# Mainboard_Encoder_Interface.net
KiCad netlist of a schematic drawn in Altium Designer
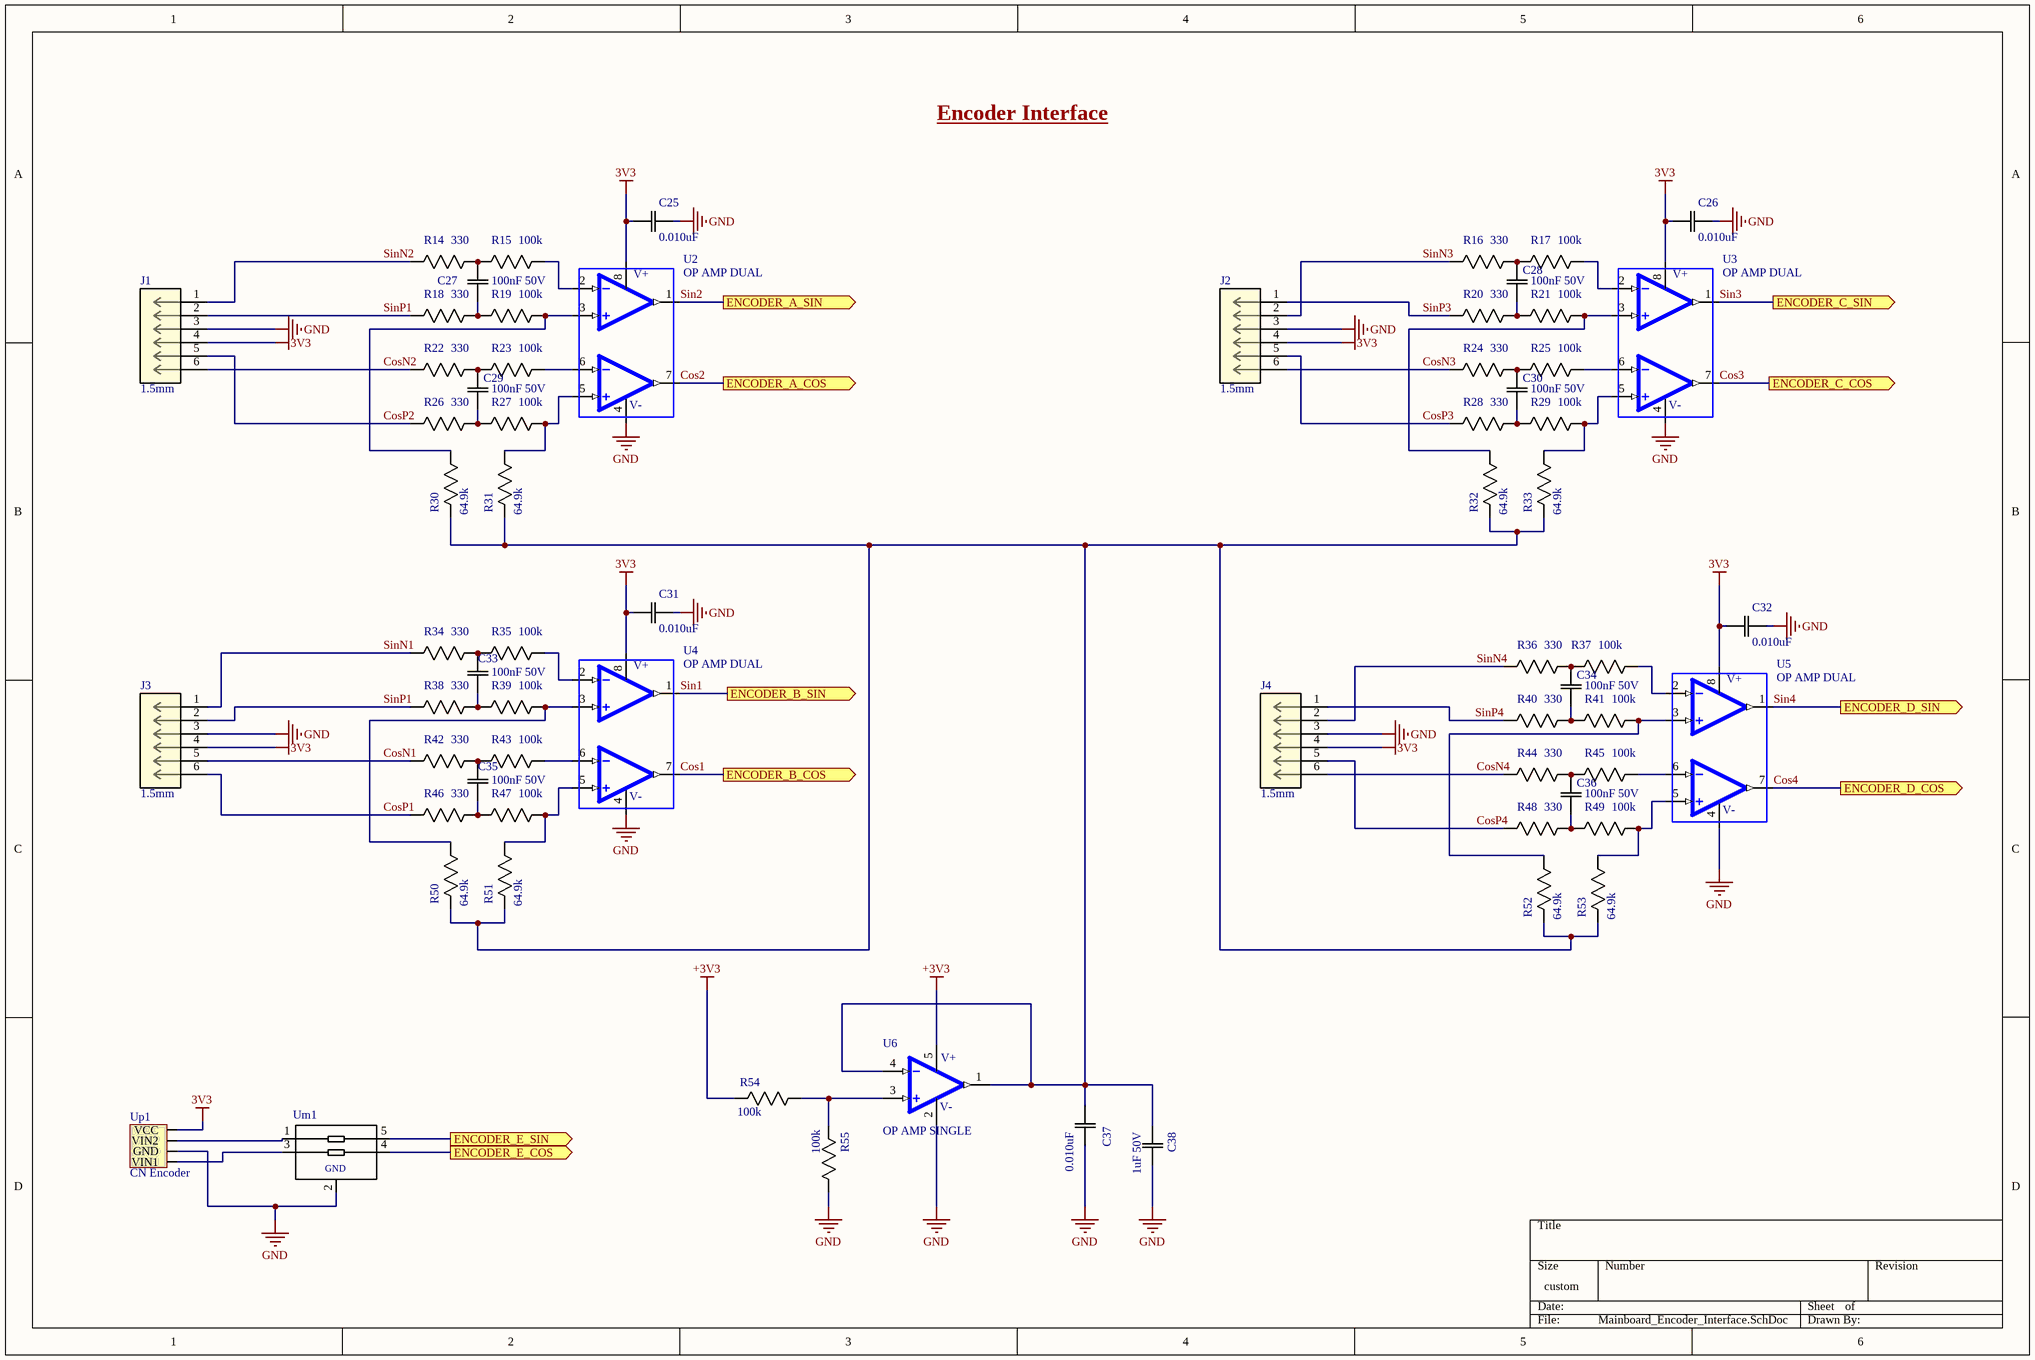
[diagram p0: Mainboard_Encoder_Interface.SchDoc]

(export (version "E")
  (design (tool "Eeschema 10.0.6"))
  (components
    (comp (ref "C25")
      (value "0.010uF")
      (footprint "0805")
      (description "CAP CER 0.010UF 50V X7R 0603/0805")
      (fields (field (name "TOLERANCE") "10%"))
      (libsource (lib "AltiumLibraries") (part "CAP 0.010uF 50V"))
    )
    (comp (ref "C26")
      (value "0.010uF")
      (footprint "0805")
      (description "CAP CER 0.010UF 50V X7R 0603/0805")
      (fields (field (name "TOLERANCE") "10%"))
      (libsource (lib "AltiumLibraries") (part "CAP 0.010uF 50V"))
    )
    (comp (ref "C27")
      (value "100nF 50V")
      (footprint "0805")
      (description "CAP CER 0.1UF 50V X7R 0805")
      (fields (field (name "TOLERANCE") "10%"))
      (libsource (lib "AltiumLibraries") (part "CAP 100nF 50V"))
    )
    (comp (ref "C28")
      (value "100nF 50V")
      (footprint "0805")
      (description "CAP CER 0.1UF 50V X7R 0805")
      (fields (field (name "TOLERANCE") "10%"))
      (libsource (lib "") (part "CAP 100nF 50V_2"))
    )
    (comp (ref "C29")
      (value "100nF 50V")
      (footprint "0805")
      (description "CAP CER 0.1UF 50V X7R 0805")
      (fields (field (name "TOLERANCE") "10%"))
      (libsource (lib "AltiumLibraries") (part "CAP 100nF 50V"))
    )
    (comp (ref "C30")
      (value "100nF 50V")
      (footprint "0805")
      (description "CAP CER 0.1UF 50V X7R 0805")
      (fields (field (name "TOLERANCE") "10%"))
      (libsource (lib "") (part "CAP 100nF 50V_2"))
    )
    (comp (ref "C31")
      (value "0.010uF")
      (footprint "0805")
      (description "CAP CER 0.010UF 50V X7R 0603/0805")
      (fields (field (name "TOLERANCE") "10%"))
      (libsource (lib "AltiumLibraries") (part "CAP 0.010uF 50V"))
    )
    (comp (ref "C32")
      (value "0.010uF")
      (footprint "0805")
      (description "CAP CER 0.010UF 50V X7R 0603/0805")
      (fields (field (name "TOLERANCE") "10%"))
      (libsource (lib "AltiumLibraries") (part "CAP 0.010uF 50V"))
    )
    (comp (ref "C33")
      (value "100nF 50V")
      (footprint "0805")
      (description "CAP CER 0.1UF 50V X7R 0805")
      (fields (field (name "TOLERANCE") "10%"))
      (libsource (lib "") (part "CAP 100nF 50V_1"))
    )
    (comp (ref "C34")
      (value "100nF 50V")
      (footprint "0805")
      (description "CAP CER 0.1UF 50V X7R 0805")
      (fields (field (name "TOLERANCE") "10%"))
      (libsource (lib "AltiumLibraries") (part "CAP 100nF 50V"))
    )
    (comp (ref "C35")
      (value "100nF 50V")
      (footprint "0805")
      (description "CAP CER 0.1UF 50V X7R 0805")
      (fields (field (name "TOLERANCE") "10%"))
      (libsource (lib "") (part "CAP 100nF 50V_1"))
    )
    (comp (ref "C36")
      (value "100nF 50V")
      (footprint "0805")
      (description "CAP CER 0.1UF 50V X7R 0805")
      (fields (field (name "TOLERANCE") "10%"))
      (libsource (lib "AltiumLibraries") (part "CAP 100nF 50V"))
    )
    (comp (ref "C37")
      (value "0.010uF")
      (footprint "0805")
      (description "CAP CER 0.010UF 50V X7R 0603/0805")
      (fields (field (name "TOLERANCE") "10%"))
      (libsource (lib "AltiumLibraries") (part "CAP 0.010uF 50V"))
    )
    (comp (ref "C38")
      (value "1uF 50V")
      (footprint "0805")
      (description "CAP CER 1UF 50V X7R 0805")
      (fields (field (name "TOLERANCE") "10%"))
      (libsource (lib "AltiumLibraries") (part "CAP 1uF 50V"))
    )
    (comp (ref "J1")
      (value "1.5mm")
      (footprint "6POS JST")
      (description "Conn Shrouded Header HDR 6 POS 1.5mm Solder RA Thru-Hole Box")
      (fields (field (name "MANUFACTURER") "JST") (field (name "MANUFACTURER PART NUMBER") "S6B-ZR(LF)(SN)"))
      (libsource (lib "AltiumLibraries") (part "CN 6POS JST RA"))
    )
    (comp (ref "J2")
      (value "1.5mm")
      (footprint "6POS JST")
      (description "Conn Shrouded Header HDR 6 POS 1.5mm Solder RA Thru-Hole Box")
      (fields (field (name "MANUFACTURER") "JST") (field (name "MANUFACTURER PART NUMBER") "S6B-ZR(LF)(SN)"))
      (libsource (lib "AltiumLibraries") (part "CN 6POS JST RA"))
    )
    (comp (ref "J3")
      (value "1.5mm")
      (footprint "6POS JST")
      (description "Conn Shrouded Header HDR 6 POS 1.5mm Solder RA Thru-Hole Box")
      (fields (field (name "MANUFACTURER") "JST") (field (name "MANUFACTURER PART NUMBER") "S6B-ZR(LF)(SN)"))
      (libsource (lib "AltiumLibraries") (part "CN 6POS JST RA"))
    )
    (comp (ref "J4")
      (value "1.5mm")
      (footprint "6POS JST")
      (description "Conn Shrouded Header HDR 6 POS 1.5mm Solder RA Thru-Hole Box")
      (fields (field (name "MANUFACTURER") "JST") (field (name "MANUFACTURER PART NUMBER") "S6B-ZR(LF)(SN)"))
      (libsource (lib "AltiumLibraries") (part "CN 6POS JST RA"))
    )
    (comp (ref "R14")
      (value "330")
      (footprint "0805")
      (description "RES SMD 330 OHM 1% 1/8W 0805")
      (fields (field (name "TOLERANCE") "1%"))
      (libsource (lib "AltiumLibraries") (part "RES 330.0 1/8W - 1%"))
    )
    (comp (ref "R15")
      (value "100k")
      (footprint "0805")
      (description "RES SMD 100K OHM 1% 1/8W 0805")
      (fields (field (name "TOLERANCE") "1%"))
      (libsource (lib "AltiumLibraries") (part "RES 100k 1/8W - 1%"))
    )
    (comp (ref "R16")
      (value "330")
      (footprint "0805")
      (description "RES SMD 330 OHM 1% 1/8W 0805")
      (fields (field (name "TOLERANCE") "1%"))
      (libsource (lib "AltiumLibraries") (part "RES 330.0 1/8W - 1%"))
    )
    (comp (ref "R17")
      (value "100k")
      (footprint "0805")
      (description "RES SMD 100K OHM 1% 1/8W 0805")
      (fields (field (name "TOLERANCE") "1%"))
      (libsource (lib "AltiumLibraries") (part "RES 100k 1/8W - 1%"))
    )
    (comp (ref "R18")
      (value "330")
      (footprint "0805")
      (description "RES SMD 330 OHM 1% 1/8W 0805")
      (fields (field (name "TOLERANCE") "1%"))
      (libsource (lib "") (part "RES 330.0 1/8W - 1%_1"))
    )
    (comp (ref "R19")
      (value "100k")
      (footprint "0805")
      (description "RES SMD 100K OHM 1% 1/8W 0805")
      (fields (field (name "TOLERANCE") "1%"))
      (libsource (lib "") (part "RES 100k 1/8W - 1%_1"))
    )
    (comp (ref "R20")
      (value "330")
      (footprint "0805")
      (description "RES SMD 330 OHM 1% 1/8W 0805")
      (fields (field (name "TOLERANCE") "1%"))
      (libsource (lib "") (part "RES 330.0 1/8W - 1%_1"))
    )
    (comp (ref "R21")
      (value "100k")
      (footprint "0805")
      (description "RES SMD 100K OHM 1% 1/8W 0805")
      (fields (field (name "TOLERANCE") "1%"))
      (libsource (lib "") (part "RES 100k 1/8W - 1%_1"))
    )
    (comp (ref "R22")
      (value "330")
      (footprint "0805")
      (description "RES SMD 330 OHM 1% 1/8W 0805")
      (fields (field (name "TOLERANCE") "1%"))
      (libsource (lib "AltiumLibraries") (part "RES 330.0 1/8W - 1%"))
    )
    (comp (ref "R23")
      (value "100k")
      (footprint "0805")
      (description "RES SMD 100K OHM 1% 1/8W 0805")
      (fields (field (name "TOLERANCE") "1%"))
      (libsource (lib "AltiumLibraries") (part "RES 100k 1/8W - 1%"))
    )
    (comp (ref "R24")
      (value "330")
      (footprint "0805")
      (description "RES SMD 330 OHM 1% 1/8W 0805")
      (fields (field (name "TOLERANCE") "1%"))
      (libsource (lib "AltiumLibraries") (part "RES 330.0 1/8W - 1%"))
    )
    (comp (ref "R25")
      (value "100k")
      (footprint "0805")
      (description "RES SMD 100K OHM 1% 1/8W 0805")
      (fields (field (name "TOLERANCE") "1%"))
      (libsource (lib "AltiumLibraries") (part "RES 100k 1/8W - 1%"))
    )
    (comp (ref "R26")
      (value "330")
      (footprint "0805")
      (description "RES SMD 330 OHM 1% 1/8W 0805")
      (fields (field (name "TOLERANCE") "1%"))
      (libsource (lib "") (part "RES 330.0 1/8W - 1%_1"))
    )
    (comp (ref "R27")
      (value "100k")
      (footprint "0805")
      (description "RES SMD 100K OHM 1% 1/8W 0805")
      (fields (field (name "TOLERANCE") "1%"))
      (libsource (lib "") (part "RES 100k 1/8W - 1%_1"))
    )
    (comp (ref "R28")
      (value "330")
      (footprint "0805")
      (description "RES SMD 330 OHM 1% 1/8W 0805")
      (fields (field (name "TOLERANCE") "1%"))
      (libsource (lib "") (part "RES 330.0 1/8W - 1%_1"))
    )
    (comp (ref "R29")
      (value "100k")
      (footprint "0805")
      (description "RES SMD 100K OHM 1% 1/8W 0805")
      (fields (field (name "TOLERANCE") "1%"))
      (libsource (lib "") (part "RES 100k 1/8W - 1%_1"))
    )
    (comp (ref "R30")
      (value "64.9k")
      (footprint "0805")
      (description "RES SMD 64.9K OHM 1% 1/8W 0805")
      (fields (field (name "TOLERANCE") "1%"))
      (libsource (lib "AltiumLibraries") (part "RES 64.9k 1/8W"))
    )
    (comp (ref "R31")
      (value "64.9k")
      (footprint "0805")
      (description "RES SMD 64.9K OHM 1% 1/8W 0805")
      (fields (field (name "TOLERANCE") "1%"))
      (libsource (lib "AltiumLibraries") (part "RES 64.9k 1/8W"))
    )
    (comp (ref "R32")
      (value "64.9k")
      (footprint "0805")
      (description "RES SMD 64.9K OHM 1% 1/8W 0805")
      (fields (field (name "TOLERANCE") "1%"))
      (libsource (lib "AltiumLibraries") (part "RES 64.9k 1/8W"))
    )
    (comp (ref "R33")
      (value "64.9k")
      (footprint "0805")
      (description "RES SMD 64.9K OHM 1% 1/8W 0805")
      (fields (field (name "TOLERANCE") "1%"))
      (libsource (lib "AltiumLibraries") (part "RES 64.9k 1/8W"))
    )
    (comp (ref "R34")
      (value "330")
      (footprint "0805")
      (description "RES SMD 330 OHM 1% 1/8W 0805")
      (fields (field (name "TOLERANCE") "1%"))
      (libsource (lib "AltiumLibraries") (part "RES 330.0 1/8W - 1%"))
    )
    (comp (ref "R35")
      (value "100k")
      (footprint "0805")
      (description "RES SMD 100K OHM 1% 1/8W 0805")
      (fields (field (name "TOLERANCE") "1%"))
      (libsource (lib "AltiumLibraries") (part "RES 100k 1/8W - 1%"))
    )
    (comp (ref "R36")
      (value "330")
      (footprint "0805")
      (description "RES SMD 330 OHM 1% 1/8W 0805")
      (fields (field (name "TOLERANCE") "1%"))
      (libsource (lib "AltiumLibraries") (part "RES 330.0 1/8W - 1%"))
    )
    (comp (ref "R37")
      (value "100k")
      (footprint "0805")
      (description "RES SMD 100K OHM 1% 1/8W 0805")
      (fields (field (name "TOLERANCE") "1%"))
      (libsource (lib "AltiumLibraries") (part "RES 100k 1/8W - 1%"))
    )
    (comp (ref "R38")
      (value "330")
      (footprint "0805")
      (description "RES SMD 330 OHM 1% 1/8W 0805")
      (fields (field (name "TOLERANCE") "1%"))
      (libsource (lib "") (part "RES 330.0 1/8W - 1%_1"))
    )
    (comp (ref "R39")
      (value "100k")
      (footprint "0805")
      (description "RES SMD 100K OHM 1% 1/8W 0805")
      (fields (field (name "TOLERANCE") "1%"))
      (libsource (lib "") (part "RES 100k 1/8W - 1%_1"))
    )
    (comp (ref "R40")
      (value "330")
      (footprint "0805")
      (description "RES SMD 330 OHM 1% 1/8W 0805")
      (fields (field (name "TOLERANCE") "1%"))
      (libsource (lib "") (part "RES 330.0 1/8W - 1%_1"))
    )
    (comp (ref "R41")
      (value "100k")
      (footprint "0805")
      (description "RES SMD 100K OHM 1% 1/8W 0805")
      (fields (field (name "TOLERANCE") "1%"))
      (libsource (lib "") (part "RES 100k 1/8W - 1%_1"))
    )
    (comp (ref "R42")
      (value "330")
      (footprint "0805")
      (description "RES SMD 330 OHM 1% 1/8W 0805")
      (fields (field (name "TOLERANCE") "1%"))
      (libsource (lib "AltiumLibraries") (part "RES 330.0 1/8W - 1%"))
    )
    (comp (ref "R43")
      (value "100k")
      (footprint "0805")
      (description "RES SMD 100K OHM 1% 1/8W 0805")
      (fields (field (name "TOLERANCE") "1%"))
      (libsource (lib "AltiumLibraries") (part "RES 100k 1/8W - 1%"))
    )
    (comp (ref "R44")
      (value "330")
      (footprint "0805")
      (description "RES SMD 330 OHM 1% 1/8W 0805")
      (fields (field (name "TOLERANCE") "1%"))
      (libsource (lib "AltiumLibraries") (part "RES 330.0 1/8W - 1%"))
    )
    (comp (ref "R45")
      (value "100k")
      (footprint "0805")
      (description "RES SMD 100K OHM 1% 1/8W 0805")
      (fields (field (name "TOLERANCE") "1%"))
      (libsource (lib "AltiumLibraries") (part "RES 100k 1/8W - 1%"))
    )
    (comp (ref "R46")
      (value "330")
      (footprint "0805")
      (description "RES SMD 330 OHM 1% 1/8W 0805")
      (fields (field (name "TOLERANCE") "1%"))
      (libsource (lib "") (part "RES 330.0 1/8W - 1%_1"))
    )
    (comp (ref "R47")
      (value "100k")
      (footprint "0805")
      (description "RES SMD 100K OHM 1% 1/8W 0805")
      (fields (field (name "TOLERANCE") "1%"))
      (libsource (lib "") (part "RES 100k 1/8W - 1%_1"))
    )
    (comp (ref "R48")
      (value "330")
      (footprint "0805")
      (description "RES SMD 330 OHM 1% 1/8W 0805")
      (fields (field (name "TOLERANCE") "1%"))
      (libsource (lib "") (part "RES 330.0 1/8W - 1%_1"))
    )
    (comp (ref "R49")
      (value "100k")
      (footprint "0805")
      (description "RES SMD 100K OHM 1% 1/8W 0805")
      (fields (field (name "TOLERANCE") "1%"))
      (libsource (lib "") (part "RES 100k 1/8W - 1%_1"))
    )
    (comp (ref "R50")
      (value "64.9k")
      (footprint "0805")
      (description "RES SMD 64.9K OHM 1% 1/8W 0805")
      (fields (field (name "TOLERANCE") "1%"))
      (libsource (lib "AltiumLibraries") (part "RES 64.9k 1/8W"))
    )
    (comp (ref "R51")
      (value "64.9k")
      (footprint "0805")
      (description "RES SMD 64.9K OHM 1% 1/8W 0805")
      (fields (field (name "TOLERANCE") "1%"))
      (libsource (lib "AltiumLibraries") (part "RES 64.9k 1/8W"))
    )
    (comp (ref "R52")
      (value "64.9k")
      (footprint "0805")
      (description "RES SMD 64.9K OHM 1% 1/8W 0805")
      (fields (field (name "TOLERANCE") "1%"))
      (libsource (lib "AltiumLibraries") (part "RES 64.9k 1/8W"))
    )
    (comp (ref "R53")
      (value "64.9k")
      (footprint "0805")
      (description "RES SMD 64.9K OHM 1% 1/8W 0805")
      (fields (field (name "TOLERANCE") "1%"))
      (libsource (lib "AltiumLibraries") (part "RES 64.9k 1/8W"))
    )
    (comp (ref "R54")
      (value "100k")
      (footprint "0805")
      (description "RES SMD 100K OHM 1% 1/8W 0805")
      (fields (field (name "TOLERANCE") "1%"))
      (libsource (lib "") (part "RES 100k 1/8W - 1%_1"))
    )
    (comp (ref "R55")
      (value "100k")
      (footprint "0805")
      (description "RES SMD 100K OHM 1% 1/8W 0805")
      (fields (field (name "TOLERANCE") "1%"))
      (libsource (lib "") (part "RES 100k 1/8W - 1%_1"))
    )
    (comp (ref "U2")
      (value "OP AMP DUAL")
      (footprint "8-MSOP")
      (description "IC OPAMP VFB 50KHZ RRO 8MSOP")
      (fields
        (field (name "MANUFACTURER") "Analog Devices")
        (field (name "MANUFACTURER PART NUMBER") "ADA4505-2ARMZ")
      )
      (libsource (lib "AltiumLibraries") (part "OP AMP DUAL"))
    )
    (comp (ref "U3")
      (value "OP AMP DUAL")
      (footprint "8-MSOP")
      (description "IC OPAMP VFB 50KHZ RRO 8MSOP")
      (fields
        (field (name "MANUFACTURER") "Analog Devices")
        (field (name "MANUFACTURER PART NUMBER") "ADA4505-2ARMZ")
      )
      (libsource (lib "AltiumLibraries") (part "OP AMP DUAL"))
    )
    (comp (ref "U4")
      (value "OP AMP DUAL")
      (footprint "8-MSOP")
      (description "IC OPAMP VFB 50KHZ RRO 8MSOP")
      (fields
        (field (name "MANUFACTURER") "Analog Devices")
        (field (name "MANUFACTURER PART NUMBER") "ADA4505-2ARMZ")
      )
      (libsource (lib "AltiumLibraries") (part "OP AMP DUAL"))
    )
    (comp (ref "U5")
      (value "OP AMP DUAL")
      (footprint "8-MSOP")
      (description "IC OPAMP VFB 50KHZ RRO 8MSOP")
      (fields
        (field (name "MANUFACTURER") "Analog Devices")
        (field (name "MANUFACTURER PART NUMBER") "ADA4505-2ARMZ")
      )
      (libsource (lib "AltiumLibraries") (part "OP AMP DUAL"))
    )
    (comp (ref "U6")
      (value "OP AMP SINGLE")
      (footprint "SOT95P280X145-5N")
      (description "ANALOG DEVICES - ADA4505-1ARJZ-R7 - IC, AMPLIF. OPER., R-R, CMOS, SOT23-5")
      (fields
        (field (name "MANUFACTURER") "Analog Devices")
        (field (name "MANUFACTURER PART NUMBER") "ADA4505-1ARJZ-R7")
      )
      (libsource (lib "AltiumLibraries") (part "OP AMP SINGLE"))
    )
    (comp (ref "Um1")
      (value "EMI")
      (footprint "SOT-665")
      (description "FILTER RC(PI) 100 OHM/19PF SMD")
      (fields (field (name "MF") "Nexperia USA Inc.") (field (name "MP") "IP4256CZ5-W,115"))
      (libsource (lib "AltiumLibraries") (part "EMI FILTER IP4256CZ5-W"))
    )
    (comp (ref "Up1")
      (value "CN Encoder")
      (footprint "EncoderConnector")
      (description "CN HDR R/A 4POS 1.5MM")
      (fields (field (name "MF") "JST Sales America Inc.") (field (name "MP") "S4B-ZR(LF)(SN)"))
      (libsource (lib "AltiumLibraries") (part "CN HDR 4POS"))
    )
  )
  (nets
    (net (code "1") (name "+3V3") (class "Default")
      (node (ref "R54") (pin "2") (pinfunction "R2_2") (pintype "passive"))
      (node (ref "U6") (pin "5") (pinfunction "V+_5") (pintype "power_in"))
    )
    (net (code "2") (name "/Cos1") (class "Default")
      (node (ref "U4") (pin "7") (pinfunction "OUTB_7") (pintype "output"))
    )
    (net (code "3") (name "/Cos2") (class "Default")
      (node (ref "U2") (pin "7") (pinfunction "OUTB_7") (pintype "output"))
    )
    (net (code "4") (name "/Cos3") (class "Default")
      (node (ref "U3") (pin "7") (pinfunction "OUTB_7") (pintype "output"))
    )
    (net (code "5") (name "/Cos4") (class "Default")
      (node (ref "U5") (pin "7") (pinfunction "OUTB_7") (pintype "output"))
    )
    (net (code "6") (name "/CosN1") (class "Default")
      (node (ref "J3") (pin "5") (pinfunction "5_5") (pintype "passive"))
      (node (ref "R42") (pin "2") (pinfunction "R2_2") (pintype "passive"))
    )
    (net (code "7") (name "/CosN2") (class "Default")
      (node (ref "J1") (pin "6") (pinfunction "6_6") (pintype "passive"))
      (node (ref "R22") (pin "2") (pinfunction "R2_2") (pintype "passive"))
    )
    (net (code "8") (name "/CosN3") (class "Default")
      (node (ref "J2") (pin "6") (pinfunction "6_6") (pintype "passive"))
      (node (ref "R24") (pin "2") (pinfunction "R2_2") (pintype "passive"))
    )
    (net (code "9") (name "/CosN4") (class "Default")
      (node (ref "J4") (pin "6") (pinfunction "6_6") (pintype "passive"))
      (node (ref "R44") (pin "2") (pinfunction "R2_2") (pintype "passive"))
    )
    (net (code "10") (name "/CosP1") (class "Default")
      (node (ref "J3") (pin "6") (pinfunction "6_6") (pintype "passive"))
      (node (ref "R46") (pin "2") (pinfunction "R2_2") (pintype "passive"))
    )
    (net (code "11") (name "/CosP2") (class "Default")
      (node (ref "J1") (pin "5") (pinfunction "5_5") (pintype "passive"))
      (node (ref "R26") (pin "2") (pinfunction "R2_2") (pintype "passive"))
    )
    (net (code "12") (name "/CosP3") (class "Default")
      (node (ref "J2") (pin "5") (pinfunction "5_5") (pintype "passive"))
      (node (ref "R28") (pin "2") (pinfunction "R2_2") (pintype "passive"))
    )
    (net (code "13") (name "/CosP4") (class "Default")
      (node (ref "J4") (pin "5") (pinfunction "5_5") (pintype "passive"))
      (node (ref "R48") (pin "2") (pinfunction "R2_2") (pintype "passive"))
    )
    (net (code "14") (name "/ENCODER_E_COS") (class "Default")
      (node (ref "Um1") (pin "4") (pinfunction "P$4_4") (pintype "passive"))
    )
    (net (code "15") (name "/ENCODER_E_SIN") (class "Default")
      (node (ref "Um1") (pin "5") (pinfunction "P$5_5") (pintype "passive"))
    )
    (net (code "16") (name "/Sin1") (class "Default")
      (node (ref "U4") (pin "1") (pinfunction "OUTA_1") (pintype "output"))
    )
    (net (code "17") (name "/Sin2") (class "Default")
      (node (ref "U2") (pin "1") (pinfunction "OUTA_1") (pintype "output"))
    )
    (net (code "18") (name "/Sin3") (class "Default")
      (node (ref "U3") (pin "1") (pinfunction "OUTA_1") (pintype "output"))
    )
    (net (code "19") (name "/Sin4") (class "Default")
      (node (ref "U5") (pin "1") (pinfunction "OUTA_1") (pintype "output"))
    )
    (net (code "20") (name "/SinN1") (class "Default")
      (node (ref "J3") (pin "1") (pinfunction "1_1") (pintype "passive"))
      (node (ref "R34") (pin "2") (pinfunction "R2_2") (pintype "passive"))
    )
    (net (code "21") (name "/SinN2") (class "Default")
      (node (ref "J1") (pin "1") (pinfunction "1_1") (pintype "passive"))
      (node (ref "R14") (pin "2") (pinfunction "R2_2") (pintype "passive"))
    )
    (net (code "22") (name "/SinN3") (class "Default")
      (node (ref "J2") (pin "2") (pinfunction "2_2") (pintype "passive"))
      (node (ref "R16") (pin "2") (pinfunction "R2_2") (pintype "passive"))
    )
    (net (code "23") (name "/SinN4") (class "Default")
      (node (ref "J4") (pin "2") (pinfunction "2_2") (pintype "passive"))
      (node (ref "R36") (pin "2") (pinfunction "R2_2") (pintype "passive"))
    )
    (net (code "24") (name "/SinP1") (class "Default")
      (node (ref "J1") (pin "2") (pinfunction "2_2") (pintype "passive"))
      (node (ref "J3") (pin "2") (pinfunction "2_2") (pintype "passive"))
      (node (ref "R18") (pin "2") (pinfunction "R2_2") (pintype "passive"))
      (node (ref "R38") (pin "2") (pinfunction "R2_2") (pintype "passive"))
    )
    (net (code "25") (name "/SinP3") (class "Default")
      (node (ref "J2") (pin "1") (pinfunction "1_1") (pintype "passive"))
      (node (ref "R20") (pin "2") (pinfunction "R2_2") (pintype "passive"))
    )
    (net (code "26") (name "/SinP4") (class "Default")
      (node (ref "J4") (pin "1") (pinfunction "1_1") (pintype "passive"))
      (node (ref "R40") (pin "2") (pinfunction "R2_2") (pintype "passive"))
    )
    (net (code "27") (name "3V3") (class "Default")
      (node (ref "C25") (pin "1") (pinfunction "C1_1") (pintype "passive"))
      (node (ref "C26") (pin "1") (pinfunction "C1_1") (pintype "passive"))
      (node (ref "C31") (pin "1") (pinfunction "C1_1") (pintype "passive"))
      (node (ref "C32") (pin "1") (pinfunction "C1_1") (pintype "passive"))
      (node (ref "J1") (pin "4") (pinfunction "4_4") (pintype "passive"))
      (node (ref "J2") (pin "4") (pinfunction "4_4") (pintype "passive"))
      (node (ref "J3") (pin "4") (pinfunction "4_4") (pintype "passive"))
      (node (ref "J4") (pin "4") (pinfunction "4_4") (pintype "passive"))
      (node (ref "U2") (pin "8") (pinfunction "V+_8") (pintype "power_in"))
      (node (ref "U3") (pin "8") (pinfunction "V+_8") (pintype "power_in"))
      (node (ref "U4") (pin "8") (pinfunction "V+_8") (pintype "power_in"))
      (node (ref "U5") (pin "8") (pinfunction "V+_8") (pintype "power_in"))
      (node (ref "Up1") (pin "VCC") (pinfunction "VCC_VCC") (pintype "power_in"))
    )
    (net (code "28") (name "GND") (class "Default")
      (node (ref "C25") (pin "2") (pinfunction "C2_2") (pintype "passive"))
      (node (ref "C26") (pin "2") (pinfunction "C2_2") (pintype "passive"))
      (node (ref "C31") (pin "2") (pinfunction "C2_2") (pintype "passive"))
      (node (ref "C32") (pin "2") (pinfunction "C2_2") (pintype "passive"))
      (node (ref "C37") (pin "2") (pinfunction "C2_2") (pintype "passive"))
      (node (ref "C38") (pin "2") (pinfunction "C2_2") (pintype "passive"))
      (node (ref "J1") (pin "3") (pinfunction "3_3") (pintype "passive"))
      (node (ref "J2") (pin "3") (pinfunction "3_3") (pintype "passive"))
      (node (ref "J3") (pin "3") (pinfunction "3_3") (pintype "passive"))
      (node (ref "J4") (pin "3") (pinfunction "3_3") (pintype "passive"))
      (node (ref "R55") (pin "1") (pinfunction "R1_1") (pintype "passive"))
      (node (ref "U2") (pin "4") (pinfunction "V-_4") (pintype "power_in"))
      (node (ref "U3") (pin "4") (pinfunction "V-_4") (pintype "power_in"))
      (node (ref "U4") (pin "4") (pinfunction "V-_4") (pintype "power_in"))
      (node (ref "U5") (pin "4") (pinfunction "V-_4") (pintype "power_in"))
      (node (ref "U6") (pin "2") (pinfunction "V-_2") (pintype "power_in"))
      (node (ref "Um1") (pin "2") (pinfunction "P$2_2") (pintype "passive"))
      (node (ref "Up1") (pin "GND") (pinfunction "GND_GND") (pintype "power_in"))
    )
    (net (code "29") (name "Net-(C27-C1)") (class "Default")
      (node (ref "C27") (pin "1") (pinfunction "C1_1") (pintype "passive"))
      (node (ref "R14") (pin "1") (pinfunction "R1_1") (pintype "passive"))
      (node (ref "R15") (pin "2") (pinfunction "R2_2") (pintype "passive"))
    )
    (net (code "30") (name "Net-(C27-C2)") (class "Default")
      (node (ref "C27") (pin "2") (pinfunction "C2_2") (pintype "passive"))
      (node (ref "R18") (pin "1") (pinfunction "R1_1") (pintype "passive"))
      (node (ref "R19") (pin "2") (pinfunction "R2_2") (pintype "passive"))
    )
    (net (code "31") (name "Net-(C28-C1)") (class "Default")
      (node (ref "C28") (pin "1") (pinfunction "C1_1") (pintype "passive"))
      (node (ref "R16") (pin "1") (pinfunction "R1_1") (pintype "passive"))
      (node (ref "R17") (pin "2") (pinfunction "R2_2") (pintype "passive"))
    )
    (net (code "32") (name "Net-(C28-C2)") (class "Default")
      (node (ref "C28") (pin "2") (pinfunction "C2_2") (pintype "passive"))
      (node (ref "R20") (pin "1") (pinfunction "R1_1") (pintype "passive"))
      (node (ref "R21") (pin "2") (pinfunction "R2_2") (pintype "passive"))
    )
    (net (code "33") (name "Net-(C29-C1)") (class "Default")
      (node (ref "C29") (pin "1") (pinfunction "C1_1") (pintype "passive"))
      (node (ref "R22") (pin "1") (pinfunction "R1_1") (pintype "passive"))
      (node (ref "R23") (pin "2") (pinfunction "R2_2") (pintype "passive"))
    )
    (net (code "34") (name "Net-(C29-C2)") (class "Default")
      (node (ref "C29") (pin "2") (pinfunction "C2_2") (pintype "passive"))
      (node (ref "R26") (pin "1") (pinfunction "R1_1") (pintype "passive"))
      (node (ref "R27") (pin "2") (pinfunction "R2_2") (pintype "passive"))
    )
    (net (code "35") (name "Net-(C30-C1)") (class "Default")
      (node (ref "C30") (pin "1") (pinfunction "C1_1") (pintype "passive"))
      (node (ref "R24") (pin "1") (pinfunction "R1_1") (pintype "passive"))
      (node (ref "R25") (pin "2") (pinfunction "R2_2") (pintype "passive"))
    )
    (net (code "36") (name "Net-(C30-C2)") (class "Default")
      (node (ref "C30") (pin "2") (pinfunction "C2_2") (pintype "passive"))
      (node (ref "R28") (pin "1") (pinfunction "R1_1") (pintype "passive"))
      (node (ref "R29") (pin "2") (pinfunction "R2_2") (pintype "passive"))
    )
    (net (code "37") (name "Net-(C33-C1)") (class "Default")
      (node (ref "C33") (pin "1") (pinfunction "C1_1") (pintype "passive"))
      (node (ref "R34") (pin "1") (pinfunction "R1_1") (pintype "passive"))
      (node (ref "R35") (pin "2") (pinfunction "R2_2") (pintype "passive"))
    )
    (net (code "38") (name "Net-(C33-C2)") (class "Default")
      (node (ref "C33") (pin "2") (pinfunction "C2_2") (pintype "passive"))
      (node (ref "R38") (pin "1") (pinfunction "R1_1") (pintype "passive"))
      (node (ref "R39") (pin "2") (pinfunction "R2_2") (pintype "passive"))
    )
    (net (code "39") (name "Net-(C34-C1)") (class "Default")
      (node (ref "C34") (pin "1") (pinfunction "C1_1") (pintype "passive"))
      (node (ref "R36") (pin "1") (pinfunction "R1_1") (pintype "passive"))
      (node (ref "R37") (pin "2") (pinfunction "R2_2") (pintype "passive"))
    )
    (net (code "40") (name "Net-(C34-C2)") (class "Default")
      (node (ref "C34") (pin "2") (pinfunction "C2_2") (pintype "passive"))
      (node (ref "R40") (pin "1") (pinfunction "R1_1") (pintype "passive"))
      (node (ref "R41") (pin "2") (pinfunction "R2_2") (pintype "passive"))
    )
    (net (code "41") (name "Net-(C35-C1)") (class "Default")
      (node (ref "C35") (pin "1") (pinfunction "C1_1") (pintype "passive"))
      (node (ref "R42") (pin "1") (pinfunction "R1_1") (pintype "passive"))
      (node (ref "R43") (pin "2") (pinfunction "R2_2") (pintype "passive"))
    )
    (net (code "42") (name "Net-(C35-C2)") (class "Default")
      (node (ref "C35") (pin "2") (pinfunction "C2_2") (pintype "passive"))
      (node (ref "R46") (pin "1") (pinfunction "R1_1") (pintype "passive"))
      (node (ref "R47") (pin "2") (pinfunction "R2_2") (pintype "passive"))
    )
    (net (code "43") (name "Net-(C36-C1)") (class "Default")
      (node (ref "C36") (pin "1") (pinfunction "C1_1") (pintype "passive"))
      (node (ref "R44") (pin "1") (pinfunction "R1_1") (pintype "passive"))
      (node (ref "R45") (pin "2") (pinfunction "R2_2") (pintype "passive"))
    )
    (net (code "44") (name "Net-(C36-C2)") (class "Default")
      (node (ref "C36") (pin "2") (pinfunction "C2_2") (pintype "passive"))
      (node (ref "R48") (pin "1") (pinfunction "R1_1") (pintype "passive"))
      (node (ref "R49") (pin "2") (pinfunction "R2_2") (pintype "passive"))
    )
    (net (code "45") (name "Net-(C37-C1)") (class "Default")
      (node (ref "C37") (pin "1") (pinfunction "C1_1") (pintype "passive"))
      (node (ref "C38") (pin "1") (pinfunction "C1_1") (pintype "passive"))
      (node (ref "R30") (pin "2") (pinfunction "R2_2") (pintype "passive"))
      (node (ref "R31") (pin "2") (pinfunction "R2_2") (pintype "passive"))
      (node (ref "R32") (pin "2") (pinfunction "R2_2") (pintype "passive"))
      (node (ref "R33") (pin "2") (pinfunction "R2_2") (pintype "passive"))
      (node (ref "R50") (pin "2") (pinfunction "R2_2") (pintype "passive"))
      (node (ref "R51") (pin "2") (pinfunction "R2_2") (pintype "passive"))
      (node (ref "R52") (pin "2") (pinfunction "R2_2") (pintype "passive"))
      (node (ref "R53") (pin "2") (pinfunction "R2_2") (pintype "passive"))
      (node (ref "U6") (pin "1") (pinfunction "OUT_1") (pintype "output"))
      (node (ref "U6") (pin "4") (pinfunction "IN-_4") (pintype "input"))
    )
    (net (code "46") (name "Net-(R15-R1)") (class "Default")
      (node (ref "R15") (pin "1") (pinfunction "R1_1") (pintype "passive"))
      (node (ref "U2") (pin "2") (pinfunction "INA-_2") (pintype "input"))
    )
    (net (code "47") (name "Net-(R17-R1)") (class "Default")
      (node (ref "R17") (pin "1") (pinfunction "R1_1") (pintype "passive"))
      (node (ref "U3") (pin "2") (pinfunction "INA-_2") (pintype "input"))
    )
    (net (code "48") (name "Net-(R19-R1)") (class "Default")
      (node (ref "R19") (pin "1") (pinfunction "R1_1") (pintype "passive"))
      (node (ref "R30") (pin "1") (pinfunction "R1_1") (pintype "passive"))
      (node (ref "U2") (pin "3") (pinfunction "INA+_3") (pintype "input"))
    )
    (net (code "49") (name "Net-(R21-R1)") (class "Default")
      (node (ref "R21") (pin "1") (pinfunction "R1_1") (pintype "passive"))
      (node (ref "R32") (pin "1") (pinfunction "R1_1") (pintype "passive"))
      (node (ref "U3") (pin "3") (pinfunction "INA+_3") (pintype "input"))
    )
    (net (code "50") (name "Net-(R23-R1)") (class "Default")
      (node (ref "R23") (pin "1") (pinfunction "R1_1") (pintype "passive"))
      (node (ref "U2") (pin "6") (pinfunction "INB-_6") (pintype "input"))
    )
    (net (code "51") (name "Net-(R25-R1)") (class "Default")
      (node (ref "R25") (pin "1") (pinfunction "R1_1") (pintype "passive"))
      (node (ref "U3") (pin "6") (pinfunction "INB-_6") (pintype "input"))
    )
    (net (code "52") (name "Net-(R27-R1)") (class "Default")
      (node (ref "R27") (pin "1") (pinfunction "R1_1") (pintype "passive"))
      (node (ref "R31") (pin "1") (pinfunction "R1_1") (pintype "passive"))
      (node (ref "U2") (pin "5") (pinfunction "INB+_5") (pintype "input"))
    )
    (net (code "53") (name "Net-(R29-R1)") (class "Default")
      (node (ref "R29") (pin "1") (pinfunction "R1_1") (pintype "passive"))
      (node (ref "R33") (pin "1") (pinfunction "R1_1") (pintype "passive"))
      (node (ref "U3") (pin "5") (pinfunction "INB+_5") (pintype "input"))
    )
    (net (code "54") (name "Net-(R35-R1)") (class "Default")
      (node (ref "R35") (pin "1") (pinfunction "R1_1") (pintype "passive"))
      (node (ref "U4") (pin "2") (pinfunction "INA-_2") (pintype "input"))
    )
    (net (code "55") (name "Net-(R37-R1)") (class "Default")
      (node (ref "R37") (pin "1") (pinfunction "R1_1") (pintype "passive"))
      (node (ref "U5") (pin "2") (pinfunction "INA-_2") (pintype "input"))
    )
    (net (code "56") (name "Net-(R39-R1)") (class "Default")
      (node (ref "R39") (pin "1") (pinfunction "R1_1") (pintype "passive"))
      (node (ref "R50") (pin "1") (pinfunction "R1_1") (pintype "passive"))
      (node (ref "U4") (pin "3") (pinfunction "INA+_3") (pintype "input"))
    )
    (net (code "57") (name "Net-(R41-R1)") (class "Default")
      (node (ref "R41") (pin "1") (pinfunction "R1_1") (pintype "passive"))
      (node (ref "R52") (pin "1") (pinfunction "R1_1") (pintype "passive"))
      (node (ref "U5") (pin "3") (pinfunction "INA+_3") (pintype "input"))
    )
    (net (code "58") (name "Net-(R43-R1)") (class "Default")
      (node (ref "R43") (pin "1") (pinfunction "R1_1") (pintype "passive"))
      (node (ref "U4") (pin "6") (pinfunction "INB-_6") (pintype "input"))
    )
    (net (code "59") (name "Net-(R45-R1)") (class "Default")
      (node (ref "R45") (pin "1") (pinfunction "R1_1") (pintype "passive"))
      (node (ref "U5") (pin "6") (pinfunction "INB-_6") (pintype "input"))
    )
    (net (code "60") (name "Net-(R47-R1)") (class "Default")
      (node (ref "R47") (pin "1") (pinfunction "R1_1") (pintype "passive"))
      (node (ref "R51") (pin "1") (pinfunction "R1_1") (pintype "passive"))
      (node (ref "U4") (pin "5") (pinfunction "INB+_5") (pintype "input"))
    )
    (net (code "61") (name "Net-(R49-R1)") (class "Default")
      (node (ref "R49") (pin "1") (pinfunction "R1_1") (pintype "passive"))
      (node (ref "R53") (pin "1") (pinfunction "R1_1") (pintype "passive"))
      (node (ref "U5") (pin "5") (pinfunction "INB+_5") (pintype "input"))
    )
    (net (code "62") (name "Net-(R54-R1)") (class "Default")
      (node (ref "R54") (pin "1") (pinfunction "R1_1") (pintype "passive"))
      (node (ref "R55") (pin "2") (pinfunction "R2_2") (pintype "passive"))
      (node (ref "U6") (pin "3") (pinfunction "IN+_3") (pintype "input"))
    )
    (net (code "63") (name "Net-(Um1-P$1)") (class "Default")
      (node (ref "Um1") (pin "1") (pinfunction "P$1_1") (pintype "passive"))
      (node (ref "Up1") (pin "VIN2") (pinfunction "VIN2_VIN2") (pintype "input"))
    )
    (net (code "64") (name "Net-(Um1-P$3)") (class "Default")
      (node (ref "Um1") (pin "3") (pinfunction "P$3_3") (pintype "passive"))
      (node (ref "Up1") (pin "VIN1") (pinfunction "VIN1_VIN1") (pintype "input"))
    )
  )
)
